# Sheet1.net
KiCad netlist of a schematic drawn in Altium Designer
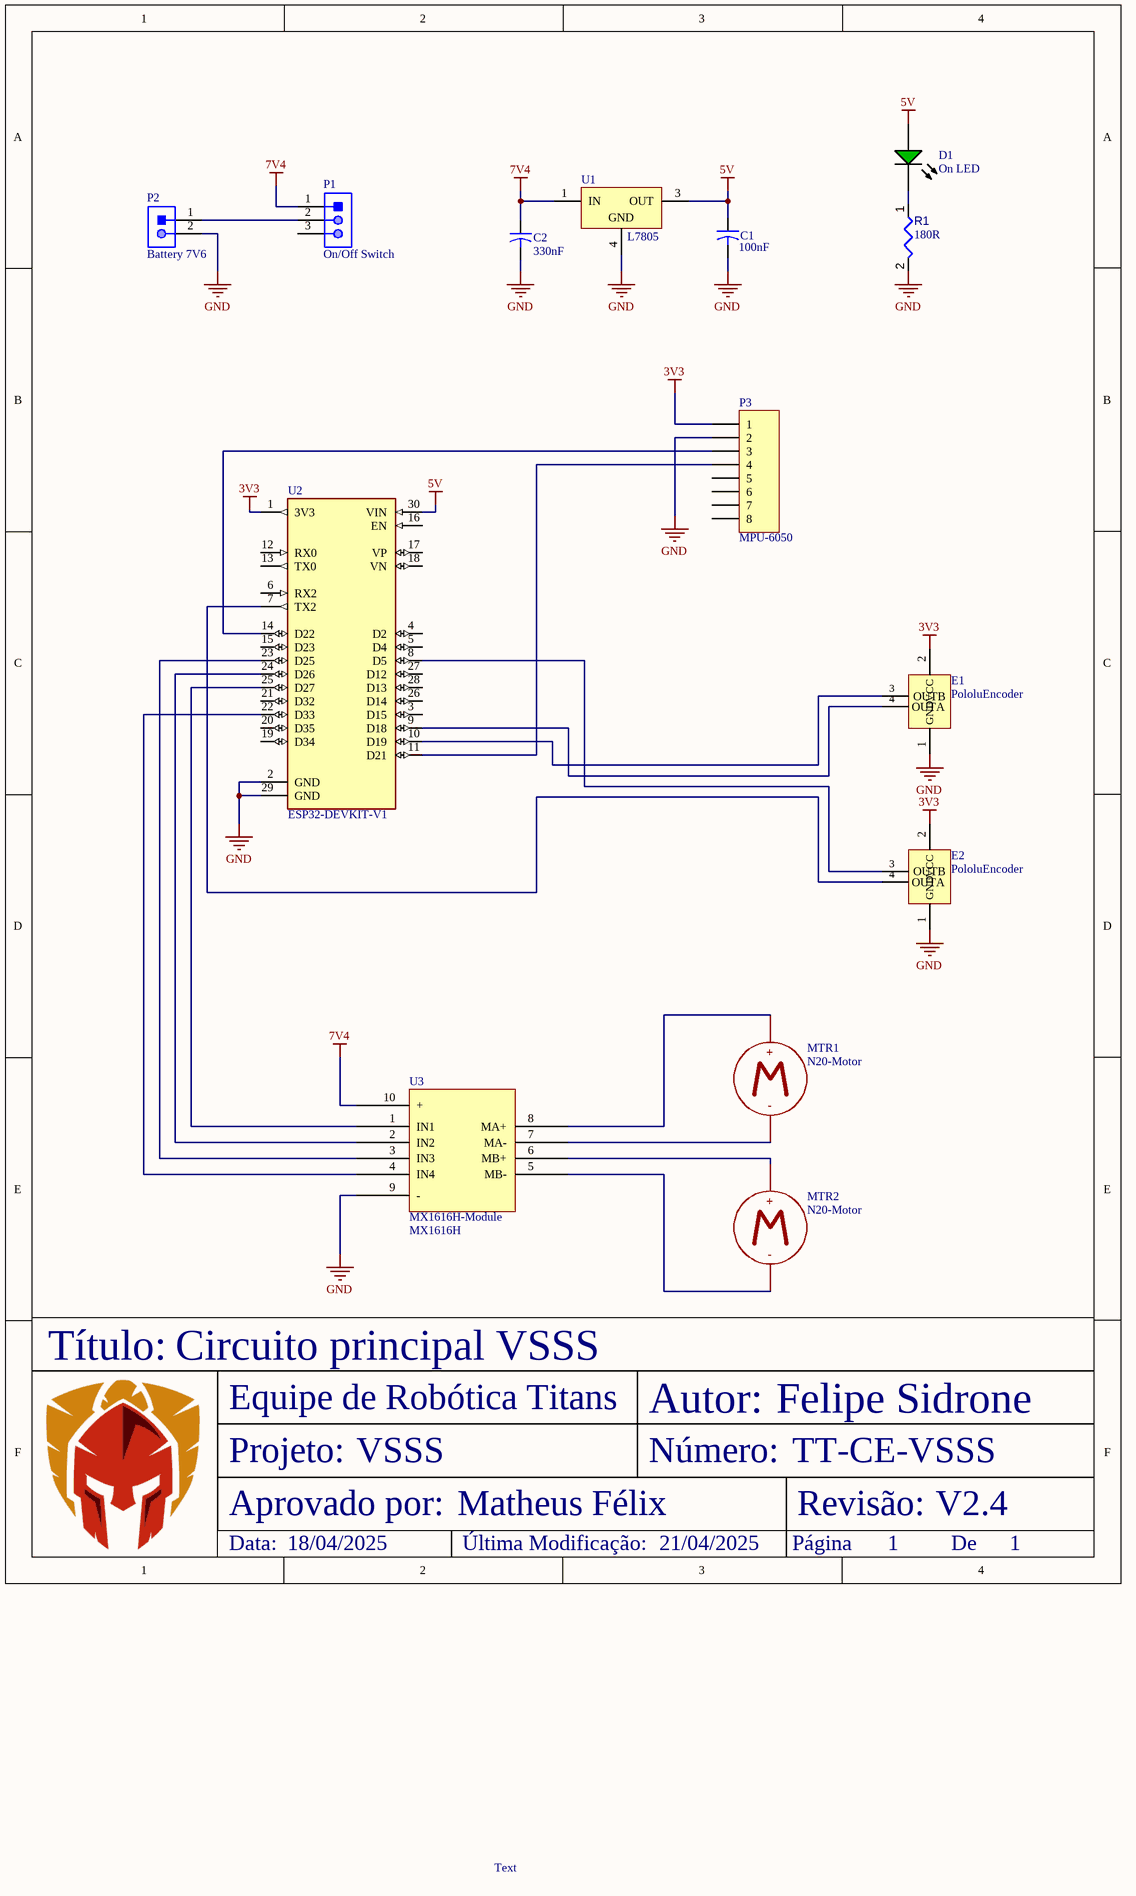
[diagram p0: Sheet1.SchDoc]

(export (version "E")
  (design (tool "Eeschema 10.0.6"))
  (components
    (comp (ref "C1")
      (value "100nF")
      (footprint "CAPR5-4X5")
      (description "Capacitor")
      (fields (field (name "Comment") "Cap2") (field (name "PUBLISHER") "Altium Limited"))
      (libsource (lib "TEE-ECAD") (part "Cap2"))
    )
    (comp (ref "C2")
      (value "330nF")
      (footprint "CAPR5-4X5")
      (description "Capacitor")
      (fields (field (name "Comment") "Cap2") (field (name "PUBLISHER") "Altium Limited"))
      (libsource (lib "TEE-ECAD") (part "Cap2"))
    )
    (comp (ref "D1")
      (value "On LED")
      (footprint "LTST-LTL-1CHG-2")
      (description "LED Uni-Color Green, 100 mW, 30 mA, -55 to 100 degC, 2-Pin THD, RoHS, Bulk")
      (fields (field (name "POWER") "100mW") (field (name "MANUFACTURER") "Lite-On"))
      (libsource (lib "TEE-ECAD") (part "LED-GREEN-AK-2"))
    )
    (comp (ref "E1")
      (value "PololuEncoder")
      (footprint "PololuEncoder")
      (description "Pololu Optical Quadrature Encoder")
      (libsource (lib "Schlib1_VSSS") (part "PololuEncoder"))
    )
    (comp (ref "E2")
      (value "PololuEncoder")
      (footprint "PololuEncoder")
      (description "Pololu Optical Quadrature Encoder")
      (libsource (lib "Schlib1_VSSS") (part "PololuEncoder"))
    )
    (comp (ref "MTR1")
      (value "N20-Motor")
      (footprint "N20-Motor_Encaixe")
      (libsource (lib "Schlib1_VSSS") (part "N20-Motor"))
    )
    (comp (ref "MTR2")
      (value "N20-Motor")
      (footprint "N20-Motor_Encaixe")
      (libsource (lib "Schlib1_VSSS") (part "N20-Motor"))
    )
    (comp (ref "P1")
      (value "On/Off Switch")
      (footprint "JST-B3P-VH(LF)(SN)-3_V")
      (fields (field (name "MANUFACTURER") "JST"))
      (libsource (lib "TEE-ECAD") (part "CN-1P-M-R3"))
    )
    (comp (ref "P2")
      (value "Battery 7V6")
      (footprint "JST-B2P-VH(LF)(SN)_V")
      (fields (field (name "MANUFACTURER") "JST"))
      (libsource (lib "TEE-ECAD") (part "CN-1P-M-R2"))
    )
    (comp (ref "P3")
      (value "MPU-6050")
      (footprint "HDR1X8")
      (description "Header, 8-Pin")
      (fields (field (name "PUBLISHER") "Altium Limited"))
      (libsource (lib "Miscellaneous Connectors") (part "Header 8"))
    )
    (comp (ref "R1")
      (value "180R")
      (footprint "RESA60-630X240")
      (description "Axial Resistor, 4.75 KOhm, +/- 1%, 0.25 W, -55 to 155 degC, 2-Pin THD, RoHS, Bulk")
      (fields (field (name "POWER") "250mW") (field (name "TOLERANCE") "1%"))
      (libsource (lib "TEE-ECAD") (part "RES-2"))
    )
    (comp (ref "U1")
      (value "L7805")
      (footprint "TO-263_L")
      (description "Positive Voltage Regulator, 3-Pin D2PAK, Tape and Reel")
      (libsource (lib "Altium Content Vault") (part "PM-REG-L4940-SOT3"))
    )
    (comp (ref "U2")
      (value "ESP32-DEVKIT-V1")
      (footprint "ESP32DEVKIT")
      (fields (field (name "MF") "Do it"))
      (libsource (lib "ESP32-DEVKIT-V1") (part "ESP32-DEVKIT-V1"))
    )
    (comp (ref "U3")
      (value "MX1616H-Module")
      (footprint "MX1616H-Module")
      (description "Full Bridge Based Peripheral Driver")
      (fields
        (field (name "MANUFACTURER") "STMicroelectronics")
        (field (name "MANUFACTURER PART NUMBER") "L298N")
        (field (name "SUPPLIER PART NUMBER") "MX1616H")
      )
      (libsource (lib "Schlib1_VSSS") (part "MX1616H-Module"))
    )
  )
  (nets
    (net (code "1") (name "3V3") (class "Default")
      (node (ref "E1") (pin "2") (pinfunction "VCC_2") (pintype "passive"))
      (node (ref "E2") (pin "2") (pinfunction "VCC_2") (pintype "passive"))
      (node (ref "P3") (pin "1") (pinfunction "1_1") (pintype "passive"))
      (node (ref "U2") (pin "1") (pinfunction "3V3_1") (pintype "output"))
    )
    (net (code "2") (name "5V") (class "Default")
      (node (ref "C1") (pin "1") (pinfunction "1_1") (pintype "passive"))
      (node (ref "D1") (pin "1") (pinfunction "A_1") (pintype "passive"))
      (node (ref "U1") (pin "3") (pinfunction "OUT_3") (pintype "power_in"))
      (node (ref "U2") (pin "30") (pinfunction "VIN_30") (pintype "input"))
    )
    (net (code "3") (name "7V4") (class "Default")
      (node (ref "C2") (pin "1") (pinfunction "1_1") (pintype "passive"))
      (node (ref "P1") (pin "1") (pinfunction "1_1") (pintype "passive"))
      (node (ref "U1") (pin "1") (pinfunction "IN_1") (pintype "power_in"))
      (node (ref "U3") (pin "10") (pinfunction "+_10") (pintype "passive"))
    )
    (net (code "4") (name "GND") (class "Default")
      (node (ref "C1") (pin "2") (pinfunction "2_2") (pintype "passive"))
      (node (ref "C2") (pin "2") (pinfunction "2_2") (pintype "passive"))
      (node (ref "E1") (pin "1") (pinfunction "GND_1") (pintype "passive"))
      (node (ref "E2") (pin "1") (pinfunction "GND_1") (pintype "passive"))
      (node (ref "P2") (pin "2") (pinfunction "2_2") (pintype "passive"))
      (node (ref "P3") (pin "2") (pinfunction "2_2") (pintype "passive"))
      (node (ref "R1") (pin "2") (pinfunction "2_2") (pintype "passive"))
      (node (ref "U1") (pin "4") (pinfunction "GND_4") (pintype "power_in"))
      (node (ref "U2") (pin "2") (pinfunction "GND_2") (pintype "power_in"))
      (node (ref "U2") (pin "29") (pinfunction "GND_29") (pintype "power_in"))
      (node (ref "U3") (pin "9") (pinfunction "-_9") (pintype "passive"))
    )
    (net (code "5") (name "Net-(D1-K)") (class "Default")
      (node (ref "D1") (pin "2") (pinfunction "K_2") (pintype "passive"))
      (node (ref "R1") (pin "1") (pinfunction "1_1") (pintype "passive"))
    )
    (net (code "6") (name "Net-(E1-OUTA)") (class "Default")
      (node (ref "E1") (pin "4") (pinfunction "OUTA_4") (pintype "passive"))
      (node (ref "U2") (pin "9") (pinfunction "D18_9") (pintype "bidirectional"))
    )
    (net (code "7") (name "Net-(E1-OUTB)") (class "Default")
      (node (ref "E1") (pin "3") (pinfunction "OUTB_3") (pintype "passive"))
      (node (ref "U2") (pin "10") (pinfunction "D19_10") (pintype "bidirectional"))
    )
    (net (code "8") (name "Net-(E2-OUTA)") (class "Default")
      (node (ref "E2") (pin "4") (pinfunction "OUTA_4") (pintype "passive"))
      (node (ref "U2") (pin "7") (pinfunction "TX2_7") (pintype "output"))
    )
    (net (code "9") (name "Net-(E2-OUTB)") (class "Default")
      (node (ref "E2") (pin "3") (pinfunction "OUTB_3") (pintype "passive"))
      (node (ref "U2") (pin "8") (pinfunction "D5_8") (pintype "bidirectional"))
    )
    (net (code "10") (name "Net-(P1-Pad2)") (class "Default")
      (node (ref "P1") (pin "2") (pinfunction "2_2") (pintype "passive"))
      (node (ref "P2") (pin "1") (pinfunction "1_1") (pintype "passive"))
    )
    (net (code "11") (name "Net-(U2-D21)") (class "Default")
      (node (ref "P3") (pin "4") (pinfunction "4_4") (pintype "passive"))
      (node (ref "U2") (pin "11") (pinfunction "D21_11") (pintype "bidirectional"))
    )
    (net (code "12") (name "Net-(U2-D22)") (class "Default")
      (node (ref "P3") (pin "3") (pinfunction "3_3") (pintype "passive"))
      (node (ref "U2") (pin "14") (pinfunction "D22_14") (pintype "bidirectional"))
    )
    (net (code "13") (name "Net-(U2-D25)") (class "Default")
      (node (ref "U2") (pin "23") (pinfunction "D25_23") (pintype "bidirectional"))
      (node (ref "U3") (pin "3") (pinfunction "IN3_3") (pintype "passive"))
    )
    (net (code "14") (name "Net-(U2-D26)") (class "Default")
      (node (ref "U2") (pin "24") (pinfunction "D26_24") (pintype "bidirectional"))
      (node (ref "U3") (pin "2") (pinfunction "IN2_2") (pintype "passive"))
    )
    (net (code "15") (name "Net-(U2-D27)") (class "Default")
      (node (ref "U2") (pin "25") (pinfunction "D27_25") (pintype "bidirectional"))
      (node (ref "U3") (pin "1") (pinfunction "IN1_1") (pintype "passive"))
    )
    (net (code "16") (name "Net-(U2-D33)") (class "Default")
      (node (ref "U2") (pin "22") (pinfunction "D33_22") (pintype "bidirectional"))
      (node (ref "U3") (pin "4") (pinfunction "IN4_4") (pintype "passive"))
    )
    (net (code "17") (name "Net-(U3-MA+)") (class "Default")
      (node (ref "MTR1") (pin "1") (pintype "passive"))
      (node (ref "U3") (pin "8") (pinfunction "MA+_8") (pintype "passive"))
    )
    (net (code "18") (name "Net-(U3-MA-)") (class "Default")
      (node (ref "MTR1") (pin "2") (pintype "passive"))
      (node (ref "U3") (pin "7") (pinfunction "MA-_7") (pintype "passive"))
    )
    (net (code "19") (name "Net-(U3-MB+)") (class "Default")
      (node (ref "MTR2") (pin "1") (pintype "passive"))
      (node (ref "U3") (pin "6") (pinfunction "MB+_6") (pintype "passive"))
    )
    (net (code "20") (name "Net-(U3-MB-)") (class "Default")
      (node (ref "MTR2") (pin "2") (pintype "passive"))
      (node (ref "U3") (pin "5") (pinfunction "MB-_5") (pintype "passive"))
    )
    (net (code "21") (name "unconnected-(P1-Pad3)") (class "Default")
      (node (ref "P1") (pin "3") (pinfunction "3_3") (pintype "passive"))
    )
    (net (code "22") (name "unconnected-(P3-Pad5)") (class "Default")
      (node (ref "P3") (pin "5") (pinfunction "5_5") (pintype "passive"))
    )
    (net (code "23") (name "unconnected-(P3-Pad6)") (class "Default")
      (node (ref "P3") (pin "6") (pinfunction "6_6") (pintype "passive"))
    )
    (net (code "24") (name "unconnected-(P3-Pad7)") (class "Default")
      (node (ref "P3") (pin "7") (pinfunction "7_7") (pintype "passive"))
    )
    (net (code "25") (name "unconnected-(P3-Pad8)") (class "Default")
      (node (ref "P3") (pin "8") (pinfunction "8_8") (pintype "passive"))
    )
    (net (code "26") (name "unconnected-(U2-D2-Pad4)") (class "Default")
      (node (ref "U2") (pin "4") (pinfunction "D2_4") (pintype "bidirectional"))
    )
    (net (code "27") (name "unconnected-(U2-D4-Pad5)") (class "Default")
      (node (ref "U2") (pin "5") (pinfunction "D4_5") (pintype "bidirectional"))
    )
    (net (code "28") (name "unconnected-(U2-D12-Pad27)") (class "Default")
      (node (ref "U2") (pin "27") (pinfunction "D12_27") (pintype "bidirectional"))
    )
    (net (code "29") (name "unconnected-(U2-D13-Pad28)") (class "Default")
      (node (ref "U2") (pin "28") (pinfunction "D13_28") (pintype "bidirectional"))
    )
    (net (code "30") (name "unconnected-(U2-D14-Pad26)") (class "Default")
      (node (ref "U2") (pin "26") (pinfunction "D14_26") (pintype "bidirectional"))
    )
    (net (code "31") (name "unconnected-(U2-D15-Pad3)") (class "Default")
      (node (ref "U2") (pin "3") (pinfunction "D15_3") (pintype "bidirectional"))
    )
    (net (code "32") (name "unconnected-(U2-D23-Pad15)") (class "Default")
      (node (ref "U2") (pin "15") (pinfunction "D23_15") (pintype "bidirectional"))
    )
    (net (code "33") (name "unconnected-(U2-D32-Pad21)") (class "Default")
      (node (ref "U2") (pin "21") (pinfunction "D32_21") (pintype "bidirectional"))
    )
    (net (code "34") (name "unconnected-(U2-D34-Pad19)") (class "Default")
      (node (ref "U2") (pin "19") (pinfunction "D34_19") (pintype "bidirectional"))
    )
    (net (code "35") (name "unconnected-(U2-D35-Pad20)") (class "Default")
      (node (ref "U2") (pin "20") (pinfunction "D35_20") (pintype "bidirectional"))
    )
    (net (code "36") (name "unconnected-(U2-EN-Pad16)") (class "Default")
      (node (ref "U2") (pin "16") (pinfunction "EN_16") (pintype "input"))
    )
    (net (code "37") (name "unconnected-(U2-RX0-Pad12)") (class "Default")
      (node (ref "U2") (pin "12") (pinfunction "RX0_12") (pintype "input"))
    )
    (net (code "38") (name "unconnected-(U2-RX2-Pad6)") (class "Default")
      (node (ref "U2") (pin "6") (pinfunction "RX2_6") (pintype "input"))
    )
    (net (code "39") (name "unconnected-(U2-TX0-Pad13)") (class "Default")
      (node (ref "U2") (pin "13") (pinfunction "TX0_13") (pintype "output"))
    )
    (net (code "40") (name "unconnected-(U2-VN-Pad18)") (class "Default")
      (node (ref "U2") (pin "18") (pinfunction "VN_18") (pintype "bidirectional"))
    )
    (net (code "41") (name "unconnected-(U2-VP-Pad17)") (class "Default")
      (node (ref "U2") (pin "17") (pinfunction "VP_17") (pintype "bidirectional"))
    )
  )
)
